# Modem.net
KiCad netlist of a schematic drawn in Altium Designer
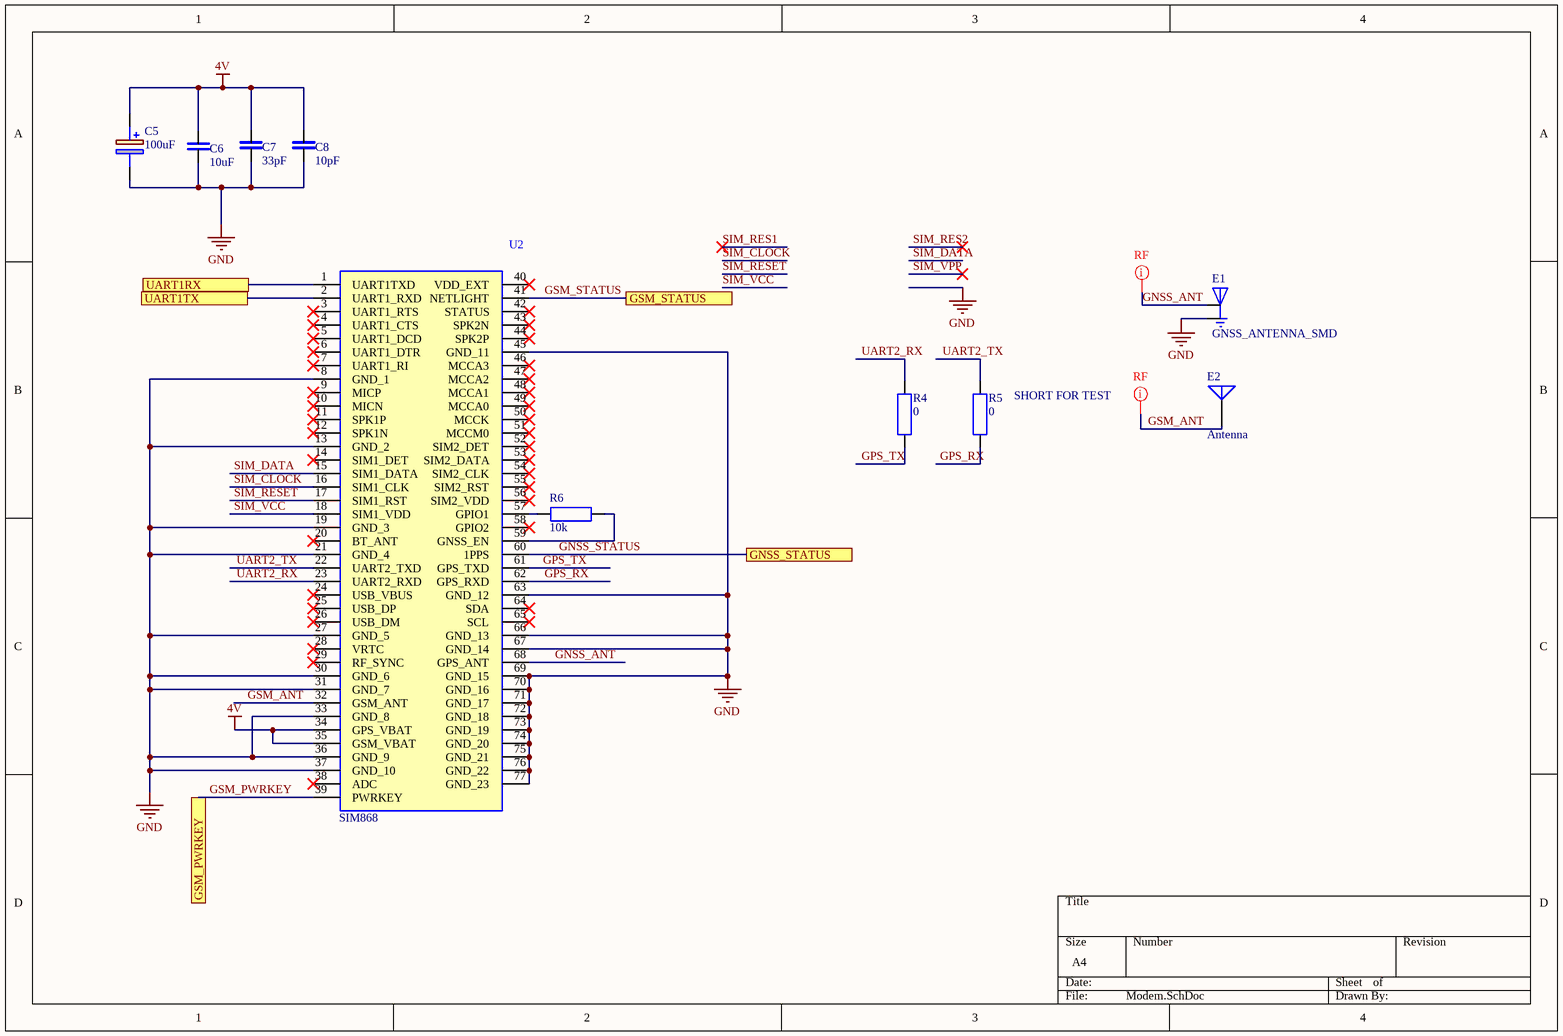
[diagram p0: Modem.SchDoc]

(export (version "E")
  (design (tool "Eeschema 10.0.6"))
  (components
    (comp (ref "C5")
      (value "100uF")
      (footprint "TANTALUM_CAP_0805")
      (description "T491C107K016AT")
      (fields (field (name "MOUSER PART NUMBER") "80-T491C107K016AT"))
      (libsource (lib "Passive_Components") (part "SMT_TANTALUM_CAP"))
    )
    (comp (ref "C6")
      (value "10uF")
      (footprint "CAP_0805")
      (fields (field (name "MP") "LD051A270KAB2A"))
      (libsource (lib "Passive_Components") (part "SMT_CAP"))
    )
    (comp (ref "C7")
      (value "33pF")
      (footprint "CAP_0805")
      (fields (field (name "MP") "LD051A270KAB2A"))
      (libsource (lib "Passive_Components") (part "SMT_CAP"))
    )
    (comp (ref "C8")
      (value "10pF")
      (footprint "CAP_0805")
      (fields (field (name "MP") "LD051A270KAB2A"))
      (libsource (lib "Passive_Components") (part "SMT_CAP"))
    )
    (comp (ref "E1")
      (value "GNSS_ANTENNA_SMD")
      (footprint "GNSS_ANTENNA_SMD")
      (description "Ceramic GNSS antenna 25*25 SMD")
      (fields (field (name "MF") "Linx") (field (name "MP") "ANT-GNSSCP-TH18L1"))
      (libsource (lib "Extras") (part "GNSS_ANTENNA_SMD"))
    )
    (comp (ref "E2")
      (value "Antenna")
      (footprint "PIN1")
      (description "Generic Antenna")
      (fields (field (name "PUBLISHER") "Altium Limited"))
      (libsource (lib "Miscellaneous Devices") (part "Antenna"))
    )
    (comp (ref "R4")
      (value "0")
      (footprint "RES_0805")
      (fields
        (field (name "MP") "2-2176053-0")
        (field (name "TOLERANCE") "1%")
        (field (name "MF") "TE Connectivity")
      )
      (libsource (lib "Passive_Components") (part "SMT_RES"))
    )
    (comp (ref "R5")
      (value "0")
      (footprint "RES_0805")
      (fields
        (field (name "MP") "2-2176053-0")
        (field (name "TOLERANCE") "1%")
        (field (name "MF") "TE Connectivity")
      )
      (libsource (lib "Passive_Components") (part "SMT_RES"))
    )
    (comp (ref "R6")
      (value "10k")
      (footprint "RES_0805")
      (fields
        (field (name "MP") "2-2176053-0")
        (field (name "TOLERANCE") "1%")
        (field (name "MF") "TE Connectivity")
      )
      (libsource (lib "Passive_Components") (part "SMT_RES"))
    )
    (comp (ref "U2")
      (value "GPRS,GSM,GNSS Modem")
      (footprint "SIM868")
      (fields (field (name "MANUFACTURER_PART_NUMBER") "SIM868") (field (name "SYMBOLNAME_1") "SIM868"))
      (libsource (lib "IC") (part "SIM868"))
    )
  )
  (nets
    (net (code "1") (name "/GNSS_ANT") (class "Default")
      (node (ref "E1") (pin "1") (pinfunction "FEEDING_1") (pintype "passive"))
      (node (ref "U2") (pin "68") (pinfunction "GPS_ANT_68") (pintype "power_in"))
    )
    (net (code "2") (name "/GNSS_STATUS") (class "Default")
      (node (ref "U2") (pin "60") (pinfunction "1PPS_60") (pintype "power_in"))
    )
    (net (code "3") (name "/GPS_RX") (class "Default")
      (node (ref "R5") (pin "1") (pinfunction "1_1") (pintype "passive"))
      (node (ref "U2") (pin "62") (pinfunction "GPS_RXD_62") (pintype "power_in"))
    )
    (net (code "4") (name "/GPS_TX") (class "Default")
      (node (ref "R4") (pin "1") (pinfunction "1_1") (pintype "passive"))
      (node (ref "U2") (pin "61") (pinfunction "GPS_TXD_61") (pintype "power_in"))
    )
    (net (code "5") (name "/GSM_ANT") (class "Default")
      (node (ref "E2") (pin "1") (pinfunction "A_1") (pintype "passive"))
      (node (ref "U2") (pin "32") (pinfunction "GSM_ANT_32") (pintype "power_in"))
    )
    (net (code "6") (name "/GSM_PWRKEY") (class "Default")
      (node (ref "U2") (pin "39") (pinfunction "PWRKEY_39") (pintype "power_in"))
    )
    (net (code "7") (name "/GSM_STATUS") (class "Default")
      (node (ref "U2") (pin "41") (pinfunction "NETLIGHT_41") (pintype "power_in"))
    )
    (net (code "8") (name "/SIM_CLOCK") (class "Default")
      (node (ref "U2") (pin "16") (pinfunction "SIM1_CLK_16") (pintype "power_in"))
    )
    (net (code "9") (name "/SIM_DATA") (class "Default")
      (node (ref "U2") (pin "15") (pinfunction "SIM1_DATA_15") (pintype "power_in"))
    )
    (net (code "12") (name "/SIM_RESET") (class "Default")
      (node (ref "U2") (pin "17") (pinfunction "SIM1_RST_17") (pintype "power_in"))
    )
    (net (code "13") (name "/SIM_VCC") (class "Default")
      (node (ref "U2") (pin "18") (pinfunction "SIM1_VDD_18") (pintype "power_in"))
    )
    (net (code "15") (name "/UART1RX") (class "Default")
      (node (ref "U2") (pin "1") (pinfunction "UART1TXD_1") (pintype "power_in"))
    )
    (net (code "16") (name "/UART1TX") (class "Default")
      (node (ref "U2") (pin "2") (pinfunction "UART1_RXD_2") (pintype "power_in"))
    )
    (net (code "17") (name "/UART2_RX") (class "Default")
      (node (ref "R4") (pin "2") (pinfunction "2_2") (pintype "passive"))
      (node (ref "U2") (pin "23") (pinfunction "UART2_RXD_23") (pintype "power_in"))
    )
    (net (code "18") (name "/UART2_TX") (class "Default")
      (node (ref "R5") (pin "2") (pinfunction "2_2") (pintype "passive"))
      (node (ref "U2") (pin "22") (pinfunction "UART2_TXD_22") (pintype "power_in"))
    )
    (net (code "19") (name "4V") (class "Default")
      (node (ref "C5") (pin "1") (pinfunction "+_1") (pintype "passive"))
      (node (ref "C6") (pin "2") (pinfunction "2_2") (pintype "passive"))
      (node (ref "C7") (pin "2") (pinfunction "2_2") (pintype "passive"))
      (node (ref "C8") (pin "2") (pinfunction "2_2") (pintype "passive"))
      (node (ref "U2") (pin "34") (pinfunction "GPS_VBAT_34") (pintype "power_in"))
      (node (ref "U2") (pin "35") (pinfunction "GSM_VBAT_35") (pintype "power_in"))
    )
    (net (code "20") (name "GND") (class "Default")
      (node (ref "C5") (pin "2") (pinfunction "-_2") (pintype "passive"))
      (node (ref "C6") (pin "1") (pinfunction "1_1") (pintype "passive"))
      (node (ref "C7") (pin "1") (pinfunction "1_1") (pintype "passive"))
      (node (ref "C8") (pin "1") (pinfunction "1_1") (pintype "passive"))
      (node (ref "E1") (pin "2") (pinfunction "GND_2") (pintype "power_in"))
      (node (ref "U2") (pin "13") (pinfunction "GND_2_13") (pintype "power_in"))
      (node (ref "U2") (pin "19") (pinfunction "GND_3_19") (pintype "power_in"))
      (node (ref "U2") (pin "21") (pinfunction "GND_4_21") (pintype "power_in"))
      (node (ref "U2") (pin "27") (pinfunction "GND_5_27") (pintype "power_in"))
      (node (ref "U2") (pin "30") (pinfunction "GND_6_30") (pintype "power_in"))
      (node (ref "U2") (pin "31") (pinfunction "GND_7_31") (pintype "power_in"))
      (node (ref "U2") (pin "33") (pinfunction "GND_8_33") (pintype "power_in"))
      (node (ref "U2") (pin "36") (pinfunction "GND_9_36") (pintype "power_in"))
      (node (ref "U2") (pin "37") (pinfunction "GND_10_37") (pintype "power_in"))
      (node (ref "U2") (pin "45") (pinfunction "GND_11_45") (pintype "power_in"))
      (node (ref "U2") (pin "63") (pinfunction "GND_12_63") (pintype "power_in"))
      (node (ref "U2") (pin "66") (pinfunction "GND_13_66") (pintype "power_in"))
      (node (ref "U2") (pin "67") (pinfunction "GND_14_67") (pintype "power_in"))
      (node (ref "U2") (pin "69") (pinfunction "GND_15_69") (pintype "power_in"))
      (node (ref "U2") (pin "70") (pinfunction "GND_16_70") (pintype "power_in"))
      (node (ref "U2") (pin "71") (pinfunction "GND_17_71") (pintype "power_in"))
      (node (ref "U2") (pin "72") (pinfunction "GND_18_72") (pintype "power_in"))
      (node (ref "U2") (pin "73") (pinfunction "GND_19_73") (pintype "power_in"))
      (node (ref "U2") (pin "74") (pinfunction "GND_20_74") (pintype "power_in"))
      (node (ref "U2") (pin "75") (pinfunction "GND_21_75") (pintype "power_in"))
      (node (ref "U2") (pin "76") (pinfunction "GND_22_76") (pintype "power_in"))
      (node (ref "U2") (pin "77") (pinfunction "GND_23_77") (pintype "power_in"))
      (node (ref "U2") (pin "8") (pinfunction "GND_1_8") (pintype "power_in"))
    )
    (net (code "21") (name "Net-(U2-GNSS_EN)") (class "Default")
      (node (ref "R6") (pin "2") (pinfunction "2_2") (pintype "passive"))
      (node (ref "U2") (pin "59") (pinfunction "GNSS_EN_59") (pintype "power_in"))
    )
    (net (code "22") (name "Net-(U2-GPIO1)") (class "Default")
      (node (ref "R6") (pin "1") (pinfunction "1_1") (pintype "passive"))
      (node (ref "U2") (pin "57") (pinfunction "GPIO1_57") (pintype "power_in"))
    )
    (net (code "23") (name "unconnected-(U2-ADC-Pad38)") (class "Default")
      (node (ref "U2") (pin "38") (pinfunction "ADC_38") (pintype "power_in+no_connect"))
    )
    (net (code "24") (name "unconnected-(U2-BT_ANT-Pad20)") (class "Default")
      (node (ref "U2") (pin "20") (pinfunction "BT_ANT_20") (pintype "power_in+no_connect"))
    )
    (net (code "25") (name "unconnected-(U2-GPIO2-Pad58)") (class "Default")
      (node (ref "U2") (pin "58") (pinfunction "GPIO2_58") (pintype "power_in+no_connect"))
    )
    (net (code "26") (name "unconnected-(U2-MCCA0-Pad49)") (class "Default")
      (node (ref "U2") (pin "49") (pinfunction "MCCA0_49") (pintype "power_in+no_connect"))
    )
    (net (code "27") (name "unconnected-(U2-MCCA1-Pad48)") (class "Default")
      (node (ref "U2") (pin "48") (pinfunction "MCCA1_48") (pintype "power_in+no_connect"))
    )
    (net (code "28") (name "unconnected-(U2-MCCA2-Pad47)") (class "Default")
      (node (ref "U2") (pin "47") (pinfunction "MCCA2_47") (pintype "power_in+no_connect"))
    )
    (net (code "29") (name "unconnected-(U2-MCCA3-Pad46)") (class "Default")
      (node (ref "U2") (pin "46") (pinfunction "MCCA3_46") (pintype "power_in+no_connect"))
    )
    (net (code "30") (name "unconnected-(U2-MCCK-Pad50)") (class "Default")
      (node (ref "U2") (pin "50") (pinfunction "MCCK_50") (pintype "power_in+no_connect"))
    )
    (net (code "31") (name "unconnected-(U2-MCCM0-Pad51)") (class "Default")
      (node (ref "U2") (pin "51") (pinfunction "MCCM0_51") (pintype "power_in+no_connect"))
    )
    (net (code "32") (name "unconnected-(U2-MICN-Pad10)") (class "Default")
      (node (ref "U2") (pin "10") (pinfunction "MICN_10") (pintype "power_in+no_connect"))
    )
    (net (code "33") (name "unconnected-(U2-MICP-Pad9)") (class "Default")
      (node (ref "U2") (pin "9") (pinfunction "MICP_9") (pintype "power_in+no_connect"))
    )
    (net (code "34") (name "unconnected-(U2-RF_SYNC-Pad29)") (class "Default")
      (node (ref "U2") (pin "29") (pinfunction "RF_SYNC_29") (pintype "power_in+no_connect"))
    )
    (net (code "35") (name "unconnected-(U2-SCL-Pad65)") (class "Default")
      (node (ref "U2") (pin "65") (pinfunction "SCL_65") (pintype "power_in+no_connect"))
    )
    (net (code "36") (name "unconnected-(U2-SDA-Pad64)") (class "Default")
      (node (ref "U2") (pin "64") (pinfunction "SDA_64") (pintype "power_in+no_connect"))
    )
    (net (code "37") (name "unconnected-(U2-SIM1_DET-Pad14)") (class "Default")
      (node (ref "U2") (pin "14") (pinfunction "SIM1_DET_14") (pintype "power_in+no_connect"))
    )
    (net (code "38") (name "unconnected-(U2-SIM2_CLK-Pad54)") (class "Default")
      (node (ref "U2") (pin "54") (pinfunction "SIM2_CLK_54") (pintype "power_in+no_connect"))
    )
    (net (code "39") (name "unconnected-(U2-SIM2_DATA-Pad53)") (class "Default")
      (node (ref "U2") (pin "53") (pinfunction "SIM2_DATA_53") (pintype "power_in+no_connect"))
    )
    (net (code "40") (name "unconnected-(U2-SIM2_DET-Pad52)") (class "Default")
      (node (ref "U2") (pin "52") (pinfunction "SIM2_DET_52") (pintype "power_in+no_connect"))
    )
    (net (code "41") (name "unconnected-(U2-SIM2_RST-Pad55)") (class "Default")
      (node (ref "U2") (pin "55") (pinfunction "SIM2_RST_55") (pintype "power_in+no_connect"))
    )
    (net (code "42") (name "unconnected-(U2-SIM2_VDD-Pad56)") (class "Default")
      (node (ref "U2") (pin "56") (pinfunction "SIM2_VDD_56") (pintype "power_in+no_connect"))
    )
    (net (code "43") (name "unconnected-(U2-SPK1N-Pad12)") (class "Default")
      (node (ref "U2") (pin "12") (pinfunction "SPK1N_12") (pintype "power_in+no_connect"))
    )
    (net (code "44") (name "unconnected-(U2-SPK1P-Pad11)") (class "Default")
      (node (ref "U2") (pin "11") (pinfunction "SPK1P_11") (pintype "power_in+no_connect"))
    )
    (net (code "45") (name "unconnected-(U2-SPK2N-Pad43)") (class "Default")
      (node (ref "U2") (pin "43") (pinfunction "SPK2N_43") (pintype "power_in+no_connect"))
    )
    (net (code "46") (name "unconnected-(U2-SPK2P-Pad44)") (class "Default")
      (node (ref "U2") (pin "44") (pinfunction "SPK2P_44") (pintype "power_in+no_connect"))
    )
    (net (code "47") (name "unconnected-(U2-STATUS-Pad42)") (class "Default")
      (node (ref "U2") (pin "42") (pinfunction "STATUS_42") (pintype "power_in+no_connect"))
    )
    (net (code "48") (name "unconnected-(U2-UART1_CTS-Pad4)") (class "Default")
      (node (ref "U2") (pin "4") (pinfunction "UART1_CTS_4") (pintype "power_in+no_connect"))
    )
    (net (code "49") (name "unconnected-(U2-UART1_DCD-Pad5)") (class "Default")
      (node (ref "U2") (pin "5") (pinfunction "UART1_DCD_5") (pintype "power_in+no_connect"))
    )
    (net (code "50") (name "unconnected-(U2-UART1_DTR-Pad6)") (class "Default")
      (node (ref "U2") (pin "6") (pinfunction "UART1_DTR_6") (pintype "power_in+no_connect"))
    )
    (net (code "51") (name "unconnected-(U2-UART1_RI-Pad7)") (class "Default")
      (node (ref "U2") (pin "7") (pinfunction "UART1_RI_7") (pintype "power_in+no_connect"))
    )
    (net (code "52") (name "unconnected-(U2-UART1_RTS-Pad3)") (class "Default")
      (node (ref "U2") (pin "3") (pinfunction "UART1_RTS_3") (pintype "power_in+no_connect"))
    )
    (net (code "53") (name "unconnected-(U2-USB_DM-Pad26)") (class "Default")
      (node (ref "U2") (pin "26") (pinfunction "USB_DM_26") (pintype "power_in+no_connect"))
    )
    (net (code "54") (name "unconnected-(U2-USB_DP-Pad25)") (class "Default")
      (node (ref "U2") (pin "25") (pinfunction "USB_DP_25") (pintype "power_in+no_connect"))
    )
    (net (code "55") (name "unconnected-(U2-USB_VBUS-Pad24)") (class "Default")
      (node (ref "U2") (pin "24") (pinfunction "USB_VBUS_24") (pintype "power_in+no_connect"))
    )
    (net (code "56") (name "unconnected-(U2-VDD_EXT-Pad40)") (class "Default")
      (node (ref "U2") (pin "40") (pinfunction "VDD_EXT_40") (pintype "power_in+no_connect"))
    )
    (net (code "57") (name "unconnected-(U2-VRTC-Pad28)") (class "Default")
      (node (ref "U2") (pin "28") (pinfunction "VRTC_28") (pintype "power_in+no_connect"))
    )
  )
)
